# roboteq_led.net
KiCad netlist of a schematic drawn in EAGLE
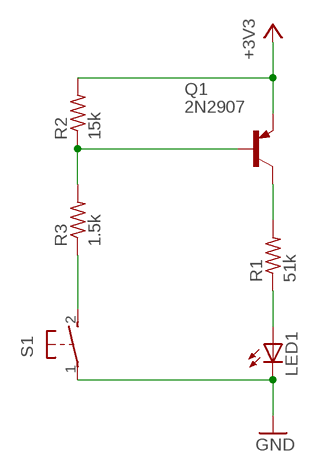
[diagram p0: schematic, sheet 1]

(export (version "E")
  (design (tool "Eeschema 10.0.6"))
  (components
    (comp (ref "LED1")
      (value "LED")
      (footprint "eagle-import:SMARTLED-TTW")
      (libsource (lib "eagle-import") (part "LED"))
    )
    (comp (ref "Q1")
      (value "2N2907")
      (footprint "eagle-import:TO92-EBC-OVAL")
      (libsource (lib "eagle-import") (part "2N2907"))
    )
    (comp (ref "R1")
      (value "51k")
      (footprint "eagle-import:0204V")
      (libsource (lib "eagle-import") (part "R-US_0204/2V"))
    )
    (comp (ref "R2")
      (value "15k")
      (footprint "eagle-import:0204V")
      (libsource (lib "eagle-import") (part "R-US_0204/2V"))
    )
    (comp (ref "R3")
      (value "1.5k")
      (footprint "eagle-import:0204V")
      (libsource (lib "eagle-import") (part "R-US_0204/2V"))
    )
    (comp (ref "S1")
      (value "31-XX")
      (footprint "eagle-import:B3F-31XX")
      (libsource (lib "eagle-import") (part "31-XX"))
    )
  )
  (nets
    (net (code "1") (name "+3V3") (class "Default")
      (node (ref "Q1") (pin "E") (pinfunction "E_E") (pintype "passive"))
      (node (ref "R2") (pin "2") (pinfunction "2_2") (pintype "passive"))
    )
    (net (code "2") (name "GND") (class "Default")
      (node (ref "LED1") (pin "C@1") (pinfunction "C_C@1") (pintype "passive"))
      (node (ref "S1") (pin "1") (pinfunction "P_1") (pintype "passive"))
    )
    (net (code "3") (name "Net-(LED1-A)") (class "Default")
      (node (ref "LED1") (pin "A@1") (pinfunction "A_A@1") (pintype "passive"))
      (node (ref "R1") (pin "1") (pinfunction "1_1") (pintype "passive"))
    )
    (net (code "4") (name "Net-(Q1-PadB)") (class "Default")
      (node (ref "Q1") (pin "B") (pinfunction "B_B") (pintype "passive"))
      (node (ref "R2") (pin "1") (pinfunction "1_1") (pintype "passive"))
      (node (ref "R3") (pin "2") (pinfunction "2_2") (pintype "passive"))
    )
    (net (code "5") (name "Net-(Q1-PadC)") (class "Default")
      (node (ref "Q1") (pin "C") (pinfunction "C_C") (pintype "passive"))
      (node (ref "R1") (pin "2") (pinfunction "2_2") (pintype "passive"))
    )
    (net (code "6") (name "Net-(S1-S)") (class "Default")
      (node (ref "R3") (pin "1") (pinfunction "1_1") (pintype "passive"))
      (node (ref "S1") (pin "2") (pinfunction "S_2") (pintype "passive"))
    )
  )
)
